# rainbow-gizmo-v2_0.net
KiCad netlist of a schematic drawn in EAGLE
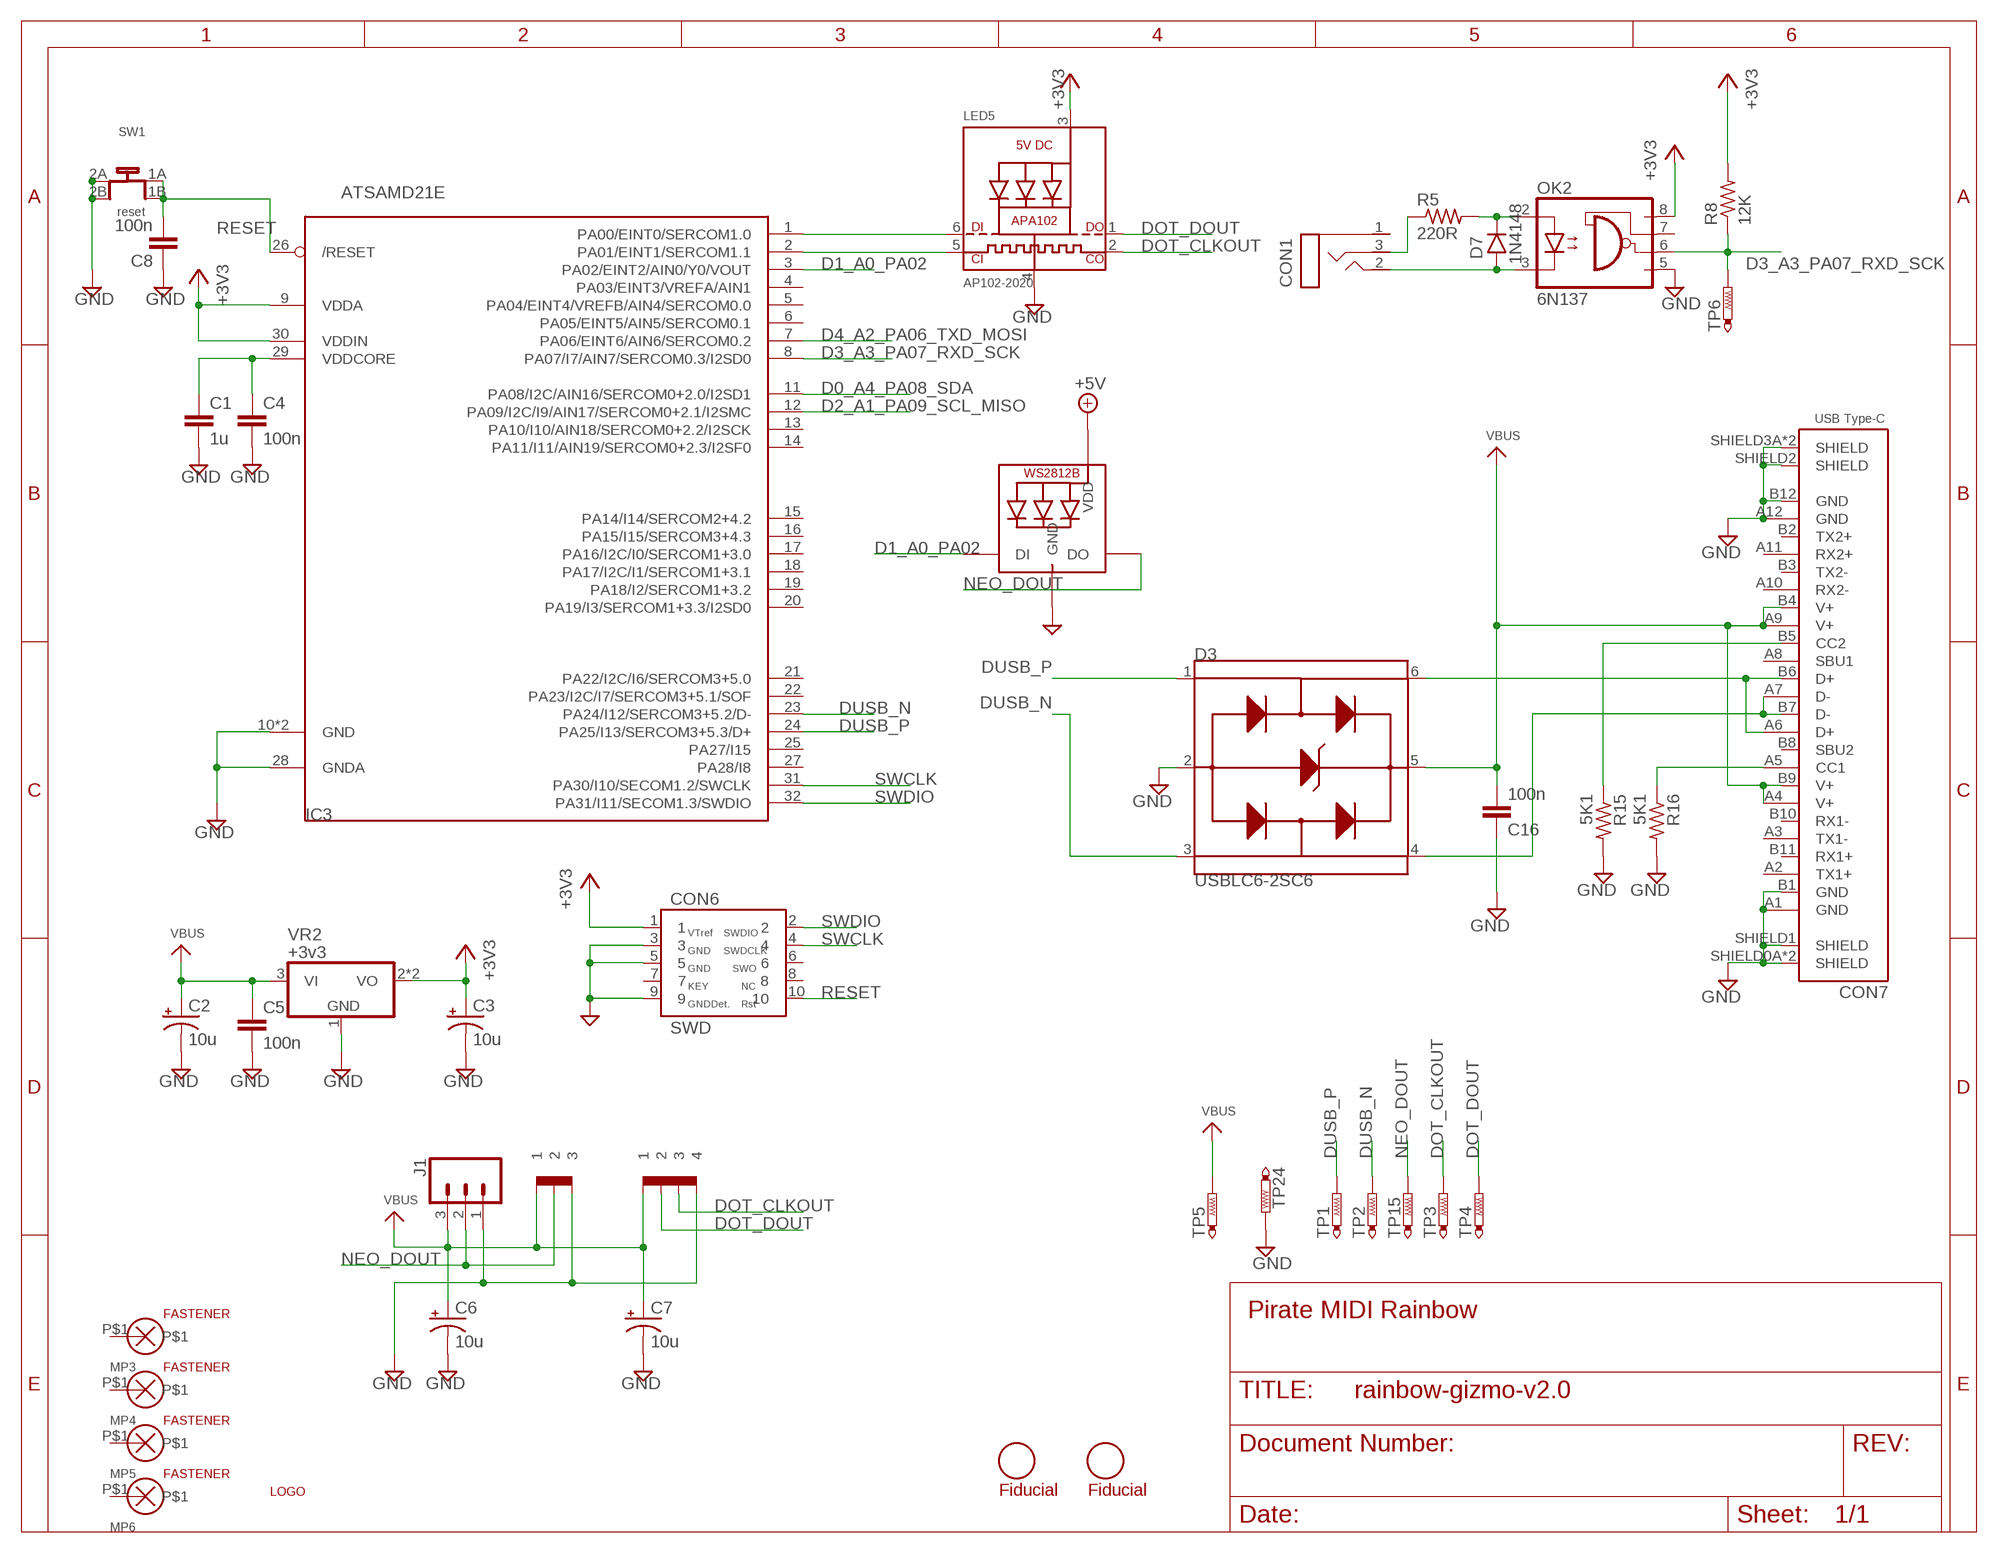
[diagram p0: schematic, sheet 1]

(export (version "E")
  (design (tool "Eeschema 10.0.6"))
  (components
    (comp (ref "C1")
      (value "1u")
      (footprint "eagle-import:0603_CAP")
      (fields
        (field (name "MANUFACTURER") "YAGEO")
        (field (name "PART_NO") "CC0603KRX5R8BB105")
        (field (name "TOLERANCE") "10%")
      )
      (libsource (lib "eagle-import") (part "SMD-NP0603-1U-H"))
    )
    (comp (ref "C2")
      (value "10u")
      (footprint "eagle-import:PANASONIC_B")
      (fields (field (name "MANUFACTURER") "PANASONIC") (field (name "PART_NO") "EEE-HB1E100AR"))
      (libsource (lib "eagle-import") (part "SMD-ELECTROLYTICB_10U"))
    )
    (comp (ref "C3")
      (value "10u")
      (footprint "eagle-import:PANASONIC_B")
      (fields (field (name "MANUFACTURER") "PANASONIC") (field (name "PART_NO") "EEE-HB1E100AR"))
      (libsource (lib "eagle-import") (part "SMD-ELECTROLYTICB_10U"))
    )
    (comp (ref "C4")
      (value "100n")
      (footprint "eagle-import:0603_CAP")
      (fields
        (field (name "MANUFACTURER") "TDK")
        (field (name "PART_NO") "CGA3E2X7R1H104K080AA")
        (field (name "TOLERANCE") "10%")
      )
      (libsource (lib "eagle-import") (part "SMD-NP0603-100N-H"))
    )
    (comp (ref "C5")
      (value "100n")
      (footprint "eagle-import:0603_CAP")
      (fields
        (field (name "MANUFACTURER") "TDK")
        (field (name "PART_NO") "CGA3E2X7R1H104K080AA")
        (field (name "TOLERANCE") "10%")
      )
      (libsource (lib "eagle-import") (part "SMD-NP0603-100N-H"))
    )
    (comp (ref "C6")
      (value "10u")
      (footprint "eagle-import:PANASONIC_B")
      (fields (field (name "MANUFACTURER") "PANASONIC") (field (name "PART_NO") "EEE-HB1E100AR"))
      (libsource (lib "eagle-import") (part "SMD-ELECTROLYTICB_10U"))
    )
    (comp (ref "C7")
      (value "10u")
      (footprint "eagle-import:PANASONIC_B")
      (fields (field (name "MANUFACTURER") "PANASONIC") (field (name "PART_NO") "EEE-HB1E100AR"))
      (libsource (lib "eagle-import") (part "SMD-ELECTROLYTICB_10U"))
    )
    (comp (ref "C8")
      (value "100n")
      (footprint "eagle-import:0603_CAP")
      (fields
        (field (name "MANUFACTURER") "TDK")
        (field (name "PART_NO") "CGA3E2X7R1H104K080AA")
        (field (name "TOLERANCE") "10%")
      )
      (libsource (lib "eagle-import") (part "SMD-NP0603-100N-H"))
    )
    (comp (ref "C16")
      (value "100n")
      (footprint "eagle-import:0603_CAP")
      (fields
        (field (name "MANUFACTURER") "TDK")
        (field (name "PART_NO") "CGA3E2X7R1H104K080AA")
        (field (name "TOLERANCE") "10%")
      )
      (libsource (lib "eagle-import") (part "SMD-NP0603-100N-H"))
    )
    (comp (ref "CON1")
      (value "TRS3.5MM")
      (footprint "eagle-import:SJ-352_-SMT")
      (fields (field (name "MANUFACTURER") "CUI") (field (name "PART_NO") "SJ-3523-SMT-TR"))
      (libsource (lib "eagle-import") (part "TRS3.5MM"))
    )
    (comp (ref "CON2")
      (value "1X3PADS")
      (footprint "eagle-import:1X3_PADS")
      (libsource (lib "eagle-import") (part "1X3PADS"))
    )
    (comp (ref "CON4")
      (value "1X4")
      (footprint "eagle-import:1X4_PADS")
      (libsource (lib "eagle-import") (part "1X4"))
    )
    (comp (ref "CON6")
      (value "SWD")
      (footprint "eagle-import:5X2_1.27MM_SMD")
      (fields (field (name "MANUFACTURER") "HARWIN") (field (name "PART_NO") "M50-3600542R"))
      (libsource (lib "eagle-import") (part "SWD_CONNECTORSMD"))
    )
    (comp (ref "CON7")
      (value "DUAL SMT")
      (footprint "eagle-import:10137064-00021LF")
      (fields (field (name "MANUFACTURER") "AMPHENOL FCI") (field (name "PART_NO") "10137064-00021LF"))
      (libsource (lib "eagle-import") (part "USB_TYPE-CAMPHENOL"))
    )
    (comp (ref "D3")
      (value "USBLC6-2SC6")
      (footprint "eagle-import:SOT95P280X145-6N")
      (fields (field (name "MANUFACTURER") "STMICROELECTRONICS"))
      (libsource (lib "eagle-import") (part "USBLC6-2SC6"))
    )
    (comp (ref "D7")
      (value "1N4148")
      (footprint "eagle-import:SOD-323")
      (fields
        (field (name "MANUFACTURER") "MICRO COMMERCIAL COMPONENTS")
        (field (name "PART_NO") "1N4148WX-TP")
      )
      (libsource (lib "eagle-import") (part "1N4148"))
    )
    (comp (ref "FD3")
      (value "FIDUCIALSQUARE_1MM")
      (footprint "eagle-import:FIDUCIAL_SQUARE_1MM")
      (libsource (lib "eagle-import") (part "FIDUCIALSQUARE_1MM"))
    )
    (comp (ref "FD4")
      (value "FIDUCIALROUND_1MM")
      (footprint "eagle-import:FIDUCIAL_ROUND_1MM")
      (libsource (lib "eagle-import") (part "FIDUCIALROUND_1MM"))
    )
    (comp (ref "IC3")
      (value "ATSAMD21E")
      (footprint "eagle-import:QFN32_5MM")
      (libsource (lib "eagle-import") (part "ATSAMD21E"))
    )
    (comp (ref "J1")
      (value "1X3PH")
      (footprint "eagle-import:JST_S3B-PH-SM4-TB")
      (libsource (lib "eagle-import") (part "1X3PH"))
    )
    (comp (ref "LED1")
      (value "WS2812B2020")
      (footprint "eagle-import:LED2020RGB")
      (fields (field (name "MANUFACTURER") "WORLDSEMI") (field (name "PART_NO") "WS2812B-2020"))
      (libsource (lib "eagle-import") (part "WS2812B2020"))
    )
    (comp (ref "LED5")
      (value "AP102-2020")
      (footprint "eagle-import:APA102_2020")
      (libsource (lib "eagle-import") (part "APA1022020"))
    )
    (comp (ref "MP3")
      (value "SCREW-FASTENER2.5")
      (footprint "eagle-import:M2.5-PANHEAD-VIA")
      (libsource (lib "eagle-import") (part "SCREW-FASTENER2.5"))
    )
    (comp (ref "MP4")
      (value "SCREW-FASTENER2.5")
      (footprint "eagle-import:M2.5-PANHEAD-VIA")
      (libsource (lib "eagle-import") (part "SCREW-FASTENER2.5"))
    )
    (comp (ref "MP5")
      (value "SCREW-FASTENER2.5")
      (footprint "eagle-import:M2.5-PANHEAD-VIA")
      (libsource (lib "eagle-import") (part "SCREW-FASTENER2.5"))
    )
    (comp (ref "MP6")
      (value "SCREW-FASTENER2.5")
      (footprint "eagle-import:M2.5-PANHEAD-VIA")
      (libsource (lib "eagle-import") (part "SCREW-FASTENER2.5"))
    )
    (comp (ref "OK2")
      (value "6N137")
      (footprint "eagle-import:SMD8")
      (fields (field (name "MANUFACTURER") "LITE-ON") (field (name "PART_NO") "6N137S"))
      (libsource (lib "eagle-import") (part "6N137S"))
    )
    (comp (ref "R5")
      (value "220R")
      (footprint "eagle-import:0603-RES")
      (fields (field (name "MANUFACTURER") "YAGEO") (field (name "PART_NO") "RC0603FR-07220RL"))
      (libsource (lib "eagle-import") (part "US0603-220R"))
    )
    (comp (ref "R8")
      (value "12K")
      (footprint "eagle-import:0603-RES")
      (fields (field (name "MANUFACTURER") "YAGEO") (field (name "PART_NO") "RC0603FR-0712KL"))
      (libsource (lib "eagle-import") (part "US0603-12K"))
    )
    (comp (ref "R15")
      (value "5K1")
      (footprint "eagle-import:0603-RES")
      (fields (field (name "MANUFACTURER") "YAGEO") (field (name "PART_NO") "RC0603FR-075K1L"))
      (libsource (lib "eagle-import") (part "US0603-5K1"))
    )
    (comp (ref "R16")
      (value "5K1")
      (footprint "eagle-import:0603-RES")
      (fields (field (name "MANUFACTURER") "YAGEO") (field (name "PART_NO") "RC0603FR-075K1L"))
      (libsource (lib "eagle-import") (part "US0603-5K1"))
    )
    (comp (ref "SW1")
      (value "reset")
      (footprint "eagle-import:KMR_X")
      (fields (field (name "MANUFACTURER") "C&K") (field (name "PART_NO") "KMR621NGLFS"))
      (libsource (lib "eagle-import") (part "MOMENTARYKRM_X"))
    )
    (comp (ref "TP1")
      (value "PTR1B1,27")
      (footprint "eagle-import:B1,27")
      (libsource (lib "eagle-import") (part "PTR1B1,27"))
    )
    (comp (ref "TP2")
      (value "PTR1B1,27")
      (footprint "eagle-import:B1,27")
      (libsource (lib "eagle-import") (part "PTR1B1,27"))
    )
    (comp (ref "TP3")
      (value "PTR1B1,27")
      (footprint "eagle-import:B1,27")
      (libsource (lib "eagle-import") (part "PTR1B1,27"))
    )
    (comp (ref "TP4")
      (value "PTR1B1,27")
      (footprint "eagle-import:B1,27")
      (libsource (lib "eagle-import") (part "PTR1B1,27"))
    )
    (comp (ref "TP5")
      (value "PTR1B1,27")
      (footprint "eagle-import:B1,27")
      (libsource (lib "eagle-import") (part "PTR1B1,27"))
    )
    (comp (ref "TP6")
      (value "PTR1B1,27")
      (footprint "eagle-import:B1,27")
      (libsource (lib "eagle-import") (part "PTR1B1,27"))
    )
    (comp (ref "TP15")
      (value "PTR1B1,27")
      (footprint "eagle-import:B1,27")
      (libsource (lib "eagle-import") (part "PTR1B1,27"))
    )
    (comp (ref "TP24")
      (value "PTR1B1,27")
      (footprint "eagle-import:B1,27")
      (libsource (lib "eagle-import") (part "PTR1B1,27"))
    )
    (comp (ref "U$5")
      (value "PM_LOGOSSTOP_M")
      (footprint "eagle-import:PM_M_MAIN_LOGO1_STOP")
      (libsource (lib "eagle-import") (part "PM_LOGOSSTOP_M"))
    )
    (comp (ref "VR2")
      (value "+3v3")
      (footprint "eagle-import:SOT223")
      (fields (field (name "MANUFACTURER") "STMICROELECTRONICS") (field (name "PART_NO") "LD1117S33CTR"))
      (libsource (lib "eagle-import") (part "LD1117"))
    )
  )
  (nets
    (net (code "1") (name "+3V3") (class "Default")
      (node (ref "C3") (pin "+") (pinfunction "+_+") (pintype "passive"))
      (node (ref "CON6") (pin "1") (pinfunction "1_1") (pintype "passive"))
      (node (ref "IC3") (pin "30") (pinfunction "VDDIN_30") (pintype "power_in"))
      (node (ref "IC3") (pin "9") (pinfunction "VDDA_9") (pintype "power_in"))
      (node (ref "LED5") (pin "3") (pinfunction "VDD_3") (pintype "power_in"))
      (node (ref "OK2") (pin "8") (pinfunction "VCC_8") (pintype "passive"))
      (node (ref "R8") (pin "2") (pinfunction "2_2") (pintype "passive"))
      (node (ref "VR2") (pin "2") (pinfunction "VO_2") (pintype "passive"))
      (node (ref "VR2") (pin "4") (pinfunction "VO_4") (pintype "passive"))
    )
    (net (code "2") (name "+5V") (class "Default")
      (node (ref "LED1") (pin "4") (pinfunction "VDD_4") (pintype "power_in"))
    )
    (net (code "3") (name "/D0_A4_PA08_SDA") (class "Default")
      (node (ref "IC3") (pin "11") (pinfunction "PA08/I2C/AIN16/SERCOM0+2.0/I2SD1_11") (pintype "bidirectional"))
    )
    (net (code "4") (name "/D1_A0_PA02") (class "Default")
      (node (ref "IC3") (pin "3") (pinfunction "PA02/EINT2/AIN0/Y0/VOUT_3") (pintype "bidirectional"))
      (node (ref "LED1") (pin "3") (pinfunction "DI_3") (pintype "input"))
    )
    (net (code "5") (name "/D2_A1_PA09_SCL_MISO") (class "Default")
      (node (ref "IC3") (pin "12") (pinfunction "PA09/I2C/I9/AIN17/SERCOM0+2.1/I2SMC_12") (pintype "bidirectional"))
    )
    (net (code "6") (name "/D3_A3_PA07_RXD_SCK") (class "Default")
      (node (ref "IC3") (pin "8") (pinfunction "PA07/I7/AIN7/SERCOM0.3/I2SD0_8") (pintype "bidirectional"))
      (node (ref "OK2") (pin "6") (pinfunction "VO_6") (pintype "passive"))
      (node (ref "R8") (pin "1") (pinfunction "1_1") (pintype "passive"))
      (node (ref "TP6") (pin "TP") (pinfunction "TP_TP") (pintype "input"))
    )
    (net (code "7") (name "/D4_A2_PA06_TXD_MOSI") (class "Default")
      (node (ref "IC3") (pin "7") (pinfunction "PA06/EINT6/AIN6/SERCOM0.2_7") (pintype "bidirectional"))
    )
    (net (code "8") (name "/DOT_CLKOUT") (class "Default")
      (node (ref "CON4") (pin "P$3") (pinfunction "3_P$3") (pintype "bidirectional"))
      (node (ref "LED5") (pin "2") (pinfunction "CKO_2") (pintype "output"))
      (node (ref "TP3") (pin "TP") (pinfunction "TP_TP") (pintype "input"))
    )
    (net (code "9") (name "/DOT_DOUT") (class "Default")
      (node (ref "CON4") (pin "P$2") (pinfunction "2_P$2") (pintype "bidirectional"))
      (node (ref "LED5") (pin "1") (pinfunction "DO_1") (pintype "output"))
      (node (ref "TP4") (pin "TP") (pinfunction "TP_TP") (pintype "input"))
    )
    (net (code "10") (name "/DUSB_N") (class "Default")
      (node (ref "D3") (pin "3") (pinfunction "I/O2_3") (pintype "bidirectional"))
      (node (ref "IC3") (pin "23") (pinfunction "PA24/I12/SERCOM3+5.2/D-_23") (pintype "bidirectional"))
      (node (ref "TP2") (pin "TP") (pinfunction "TP_TP") (pintype "input"))
    )
    (net (code "11") (name "/DUSB_P") (class "Default")
      (node (ref "D3") (pin "1") (pinfunction "I/O1_1") (pintype "bidirectional"))
      (node (ref "IC3") (pin "24") (pinfunction "PA25/I13/SERCOM3+5.3/D+_24") (pintype "bidirectional"))
      (node (ref "TP1") (pin "TP") (pinfunction "TP_TP") (pintype "input"))
    )
    (net (code "12") (name "/NEO_DOUT") (class "Default")
      (node (ref "CON2") (pin "P$2") (pinfunction "2_P$2") (pintype "bidirectional"))
      (node (ref "J1") (pin "2") (pinfunction "2_2") (pintype "passive"))
      (node (ref "LED1") (pin "1") (pinfunction "DO_1") (pintype "output"))
      (node (ref "TP15") (pin "TP") (pinfunction "TP_TP") (pintype "input"))
    )
    (net (code "13") (name "/RESET") (class "Default")
      (node (ref "C8") (pin "2") (pinfunction "2_2") (pintype "passive"))
      (node (ref "CON6") (pin "10") (pinfunction "10_10") (pintype "passive"))
      (node (ref "IC3") (pin "26") (pinfunction "/RESET_26") (pintype "bidirectional"))
      (node (ref "SW1") (pin "1A") (pinfunction "1_1A") (pintype "passive"))
      (node (ref "SW1") (pin "1B") (pinfunction "2_1B") (pintype "passive"))
    )
    (net (code "14") (name "/SWCLK") (class "Default")
      (node (ref "CON6") (pin "4") (pinfunction "4_4") (pintype "passive"))
      (node (ref "IC3") (pin "31") (pinfunction "PA30/I10/SECOM1.2/SWCLK_31") (pintype "bidirectional"))
    )
    (net (code "15") (name "/SWDIO") (class "Default")
      (node (ref "CON6") (pin "2") (pinfunction "2_2") (pintype "passive"))
      (node (ref "IC3") (pin "32") (pinfunction "PA31/I11/SECOM1.3/SWDIO_32") (pintype "bidirectional"))
    )
    (net (code "16") (name "GND") (class "Default")
      (node (ref "C1") (pin "2") (pinfunction "2_2") (pintype "passive"))
      (node (ref "C16") (pin "1") (pinfunction "1_1") (pintype "passive"))
      (node (ref "C2") (pin "-") (pinfunction "-_-") (pintype "passive"))
      (node (ref "C3") (pin "-") (pinfunction "-_-") (pintype "passive"))
      (node (ref "C4") (pin "2") (pinfunction "2_2") (pintype "passive"))
      (node (ref "C5") (pin "2") (pinfunction "2_2") (pintype "passive"))
      (node (ref "C6") (pin "-") (pinfunction "-_-") (pintype "passive"))
      (node (ref "C7") (pin "-") (pinfunction "-_-") (pintype "passive"))
      (node (ref "C8") (pin "1") (pinfunction "1_1") (pintype "passive"))
      (node (ref "CON2") (pin "P$3") (pinfunction "3_P$3") (pintype "bidirectional"))
      (node (ref "CON4") (pin "P$4") (pinfunction "4_P$4") (pintype "bidirectional"))
      (node (ref "CON6") (pin "3") (pinfunction "3_3") (pintype "passive"))
      (node (ref "CON6") (pin "5") (pinfunction "5_5") (pintype "passive"))
      (node (ref "CON6") (pin "9") (pinfunction "9_9") (pintype "passive"))
      (node (ref "CON7") (pin "A1") (pinfunction "GND_A1") (pintype "power_in"))
      (node (ref "CON7") (pin "A12") (pinfunction "GND_A12") (pintype "power_in"))
      (node (ref "CON7") (pin "B1") (pinfunction "GND_B1") (pintype "power_in"))
      (node (ref "CON7") (pin "B12") (pinfunction "GND_B12") (pintype "power_in"))
      (node (ref "CON7") (pin "SHIELD0A") (pinfunction "SHIELD_SHIELD0A") (pintype "bidirectional"))
      (node (ref "CON7") (pin "SHIELD0B") (pinfunction "SHIELD_SHIELD0B") (pintype "bidirectional"))
      (node (ref "CON7") (pin "SHIELD1") (pinfunction "SHIELD_SHIELD1") (pintype "bidirectional"))
      (node (ref "CON7") (pin "SHIELD2") (pinfunction "SHIELD_SHIELD2") (pintype "bidirectional"))
      (node (ref "CON7") (pin "SHIELD3A") (pinfunction "SHIELD_SHIELD3A") (pintype "bidirectional"))
      (node (ref "CON7") (pin "SHIELD3B") (pinfunction "SHIELD_SHIELD3B") (pintype "bidirectional"))
      (node (ref "D3") (pin "2") (pinfunction "GND_2") (pintype "power_in"))
      (node (ref "IC3") (pin "10") (pinfunction "GND_10") (pintype "power_in"))
      (node (ref "IC3") (pin "28") (pinfunction "GNDA_28") (pintype "power_in"))
      (node (ref "IC3") (pin "33") (pinfunction "GND_33") (pintype "power_in"))
      (node (ref "J1") (pin "1") (pinfunction "1_1") (pintype "passive"))
      (node (ref "LED1") (pin "2") (pinfunction "GND_2") (pintype "power_in"))
      (node (ref "LED5") (pin "4") (pinfunction "GND_4") (pintype "power_in"))
      (node (ref "OK2") (pin "5") (pinfunction "GND_5") (pintype "passive"))
      (node (ref "R15") (pin "2") (pinfunction "2_2") (pintype "passive"))
      (node (ref "R16") (pin "2") (pinfunction "2_2") (pintype "passive"))
      (node (ref "SW1") (pin "2A") (pinfunction "3_2A") (pintype "passive"))
      (node (ref "SW1") (pin "2B") (pinfunction "4_2B") (pintype "passive"))
      (node (ref "TP24") (pin "TP") (pinfunction "TP_TP") (pintype "input"))
      (node (ref "VR2") (pin "1") (pinfunction "GND_1") (pintype "passive"))
    )
    (net (code "17") (name "Net-(CON1-R)") (class "Default")
      (node (ref "CON1") (pin "3") (pinfunction "R_3") (pintype "passive"))
      (node (ref "R5") (pin "1") (pinfunction "1_1") (pintype "passive"))
    )
    (net (code "18") (name "Net-(CON1-T)") (class "Default")
      (node (ref "CON1") (pin "2") (pinfunction "T_2") (pintype "passive"))
      (node (ref "D7") (pin "A") (pinfunction "A_A") (pintype "passive"))
      (node (ref "OK2") (pin "3") (pinfunction "C_3") (pintype "passive"))
    )
    (net (code "19") (name "Net-(CON7-CC1)") (class "Default")
      (node (ref "CON7") (pin "A5") (pinfunction "CC1_A5") (pintype "bidirectional"))
      (node (ref "R16") (pin "1") (pinfunction "1_1") (pintype "passive"))
    )
    (net (code "20") (name "Net-(CON7-CC2)") (class "Default")
      (node (ref "CON7") (pin "B5") (pinfunction "CC2_B5") (pintype "bidirectional"))
      (node (ref "R15") (pin "1") (pinfunction "1_1") (pintype "passive"))
    )
    (net (code "21") (name "Net-(D3-I{slash}O3)") (class "Default")
      (node (ref "CON7") (pin "A6") (pinfunction "D+_A6") (pintype "bidirectional"))
      (node (ref "CON7") (pin "B6") (pinfunction "D+_B6") (pintype "bidirectional"))
      (node (ref "D3") (pin "6") (pinfunction "I/O3_6") (pintype "bidirectional"))
    )
    (net (code "22") (name "Net-(D3-I{slash}O4)") (class "Default")
      (node (ref "CON7") (pin "A7") (pinfunction "D-_A7") (pintype "bidirectional"))
      (node (ref "CON7") (pin "B7") (pinfunction "D-_B7") (pintype "bidirectional"))
      (node (ref "D3") (pin "4") (pinfunction "I/O4_4") (pintype "bidirectional"))
    )
    (net (code "23") (name "Net-(IC3-PA00{slash}EINT0{slash}SERCOM1.0)") (class "Default")
      (node (ref "IC3") (pin "1") (pinfunction "PA00/EINT0/SERCOM1.0_1") (pintype "bidirectional"))
      (node (ref "LED5") (pin "6") (pinfunction "DI_6") (pintype "input"))
    )
    (net (code "24") (name "Net-(IC3-PA01{slash}EINT1{slash}SERCOM1.1)") (class "Default")
      (node (ref "IC3") (pin "2") (pinfunction "PA01/EINT1/SERCOM1.1_2") (pintype "bidirectional"))
      (node (ref "LED5") (pin "5") (pinfunction "CKI_5") (pintype "input"))
    )
    (net (code "25") (name "Net-(IC3-VDDCORE)") (class "Default")
      (node (ref "C1") (pin "1") (pinfunction "1_1") (pintype "passive"))
      (node (ref "C4") (pin "1") (pinfunction "1_1") (pintype "passive"))
      (node (ref "IC3") (pin "29") (pinfunction "VDDCORE_29") (pintype "power_in"))
    )
    (net (code "26") (name "Net-(OK2-A)") (class "Default")
      (node (ref "D7") (pin "C") (pinfunction "C_C") (pintype "passive"))
      (node (ref "OK2") (pin "2") (pinfunction "A_2") (pintype "passive"))
      (node (ref "R5") (pin "2") (pinfunction "2_2") (pintype "passive"))
    )
    (net (code "27") (name "VBUS") (class "Default")
      (node (ref "C16") (pin "2") (pinfunction "2_2") (pintype "passive"))
      (node (ref "C2") (pin "+") (pinfunction "+_+") (pintype "passive"))
      (node (ref "C5") (pin "1") (pinfunction "1_1") (pintype "passive"))
      (node (ref "C6") (pin "+") (pinfunction "+_+") (pintype "passive"))
      (node (ref "C7") (pin "+") (pinfunction "+_+") (pintype "passive"))
      (node (ref "CON2") (pin "P$1") (pinfunction "1_P$1") (pintype "bidirectional"))
      (node (ref "CON4") (pin "P$1") (pinfunction "1_P$1") (pintype "bidirectional"))
      (node (ref "CON7") (pin "A4") (pinfunction "V+_A4") (pintype "power_in"))
      (node (ref "CON7") (pin "A9") (pinfunction "V+_A9") (pintype "power_in"))
      (node (ref "CON7") (pin "B4") (pinfunction "V+_B4") (pintype "power_in"))
      (node (ref "CON7") (pin "B9") (pinfunction "V+_B9") (pintype "power_in"))
      (node (ref "D3") (pin "5") (pinfunction "VBUS_5") (pintype "power_in"))
      (node (ref "J1") (pin "3") (pinfunction "3_3") (pintype "passive"))
      (node (ref "TP5") (pin "TP") (pinfunction "TP_TP") (pintype "input"))
      (node (ref "VR2") (pin "3") (pinfunction "VI_3") (pintype "input"))
    )
    (net (code "28") (name "unconnected-(CON1-S-Pad1)") (class "Default")
      (node (ref "CON1") (pin "1") (pinfunction "S_1") (pintype "passive"))
    )
    (net (code "29") (name "unconnected-(CON6-Pad6)") (class "Default")
      (node (ref "CON6") (pin "6") (pinfunction "6_6") (pintype "passive"))
    )
    (net (code "30") (name "unconnected-(CON6-Pad7)") (class "Default")
      (node (ref "CON6") (pin "7") (pinfunction "7_7") (pintype "passive"))
    )
    (net (code "31") (name "unconnected-(CON6-Pad8)") (class "Default")
      (node (ref "CON6") (pin "8") (pinfunction "8_8") (pintype "passive"))
    )
    (net (code "32") (name "unconnected-(CON7-RX1+-PadB11)") (class "Default")
      (node (ref "CON7") (pin "B11") (pinfunction "RX1+_B11") (pintype "input"))
    )
    (net (code "33") (name "unconnected-(CON7-RX1--PadB10)") (class "Default")
      (node (ref "CON7") (pin "B10") (pinfunction "RX1-_B10") (pintype "input"))
    )
    (net (code "34") (name "unconnected-(CON7-RX2+-PadA11)") (class "Default")
      (node (ref "CON7") (pin "A11") (pinfunction "RX2+_A11") (pintype "input"))
    )
    (net (code "35") (name "unconnected-(CON7-RX2--PadA10)") (class "Default")
      (node (ref "CON7") (pin "A10") (pinfunction "RX2-_A10") (pintype "input"))
    )
    (net (code "36") (name "unconnected-(CON7-SBU1-PadA8)") (class "Default")
      (node (ref "CON7") (pin "A8") (pinfunction "SBU1_A8") (pintype "bidirectional"))
    )
    (net (code "37") (name "unconnected-(CON7-SBU2-PadB8)") (class "Default")
      (node (ref "CON7") (pin "B8") (pinfunction "SBU2_B8") (pintype "bidirectional"))
    )
    (net (code "38") (name "unconnected-(CON7-TX1+-PadA2)") (class "Default")
      (node (ref "CON7") (pin "A2") (pinfunction "TX1+_A2") (pintype "output"))
    )
    (net (code "39") (name "unconnected-(CON7-TX1--PadA3)") (class "Default")
      (node (ref "CON7") (pin "A3") (pinfunction "TX1-_A3") (pintype "output"))
    )
    (net (code "40") (name "unconnected-(CON7-TX2+-PadB2)") (class "Default")
      (node (ref "CON7") (pin "B2") (pinfunction "TX2+_B2") (pintype "output"))
    )
    (net (code "41") (name "unconnected-(CON7-TX2--PadB3)") (class "Default")
      (node (ref "CON7") (pin "B3") (pinfunction "TX2-_B3") (pintype "output"))
    )
    (net (code "42") (name "unconnected-(IC3-PA03{slash}EINT3{slash}VREFA{slash}AIN1-Pad4)") (class "Default")
      (node (ref "IC3") (pin "4") (pinfunction "PA03/EINT3/VREFA/AIN1_4") (pintype "bidirectional"))
    )
    (net (code "43") (name "unconnected-(IC3-PA04{slash}EINT4{slash}VREFB{slash}AIN4{slash}SERCOM0.0-Pad5)") (class "Default")
      (node (ref "IC3") (pin "5") (pinfunction "PA04/EINT4/VREFB/AIN4/SERCOM0.0_5") (pintype "bidirectional"))
    )
    (net (code "44") (name "unconnected-(IC3-PA05{slash}EINT5{slash}AIN5{slash}SERCOM0.1-Pad6)") (class "Default")
      (node (ref "IC3") (pin "6") (pinfunction "PA05/EINT5/AIN5/SERCOM0.1_6") (pintype "bidirectional"))
    )
    (net (code "45") (name "unconnected-(IC3-PA10{slash}I10{slash}AIN18{slash}SERCOM0+2.2{slash}I2SCK-Pad13)") (class "Default")
      (node (ref "IC3") (pin "13") (pinfunction "PA10/I10/AIN18/SERCOM0+2.2/I2SCK_13") (pintype "bidirectional"))
    )
    (net (code "46") (name "unconnected-(IC3-PA11{slash}I11{slash}AIN19{slash}SERCOM0+2.3{slash}I2SF0-Pad14)") (class "Default")
      (node (ref "IC3") (pin "14") (pinfunction "PA11/I11/AIN19/SERCOM0+2.3/I2SF0_14") (pintype "bidirectional"))
    )
    (net (code "47") (name "unconnected-(IC3-PA14{slash}I14{slash}SERCOM2+4.2-Pad15)") (class "Default")
      (node (ref "IC3") (pin "15") (pinfunction "PA14/I14/SERCOM2+4.2_15") (pintype "bidirectional"))
    )
    (net (code "48") (name "unconnected-(IC3-PA15{slash}I15{slash}SERCOM3+4.3-Pad16)") (class "Default")
      (node (ref "IC3") (pin "16") (pinfunction "PA15/I15/SERCOM3+4.3_16") (pintype "bidirectional"))
    )
    (net (code "49") (name "unconnected-(IC3-PA16{slash}I2C{slash}I0{slash}SERCOM1+3.0-Pad17)") (class "Default")
      (node (ref "IC3") (pin "17") (pinfunction "PA16/I2C/I0/SERCOM1+3.0_17") (pintype "bidirectional"))
    )
    (net (code "50") (name "unconnected-(IC3-PA17{slash}I2C{slash}I1{slash}SERCOM1+3.1-Pad18)") (class "Default")
      (node (ref "IC3") (pin "18") (pinfunction "PA17/I2C/I1/SERCOM1+3.1_18") (pintype "bidirectional"))
    )
    (net (code "51") (name "unconnected-(IC3-PA18{slash}I2{slash}SERCOM1+3.2-Pad19)") (class "Default")
      (node (ref "IC3") (pin "19") (pinfunction "PA18/I2/SERCOM1+3.2_19") (pintype "bidirectional"))
    )
    (net (code "52") (name "unconnected-(IC3-PA19{slash}I3{slash}SERCOM1+3.3{slash}I2SD0-Pad20)") (class "Default")
      (node (ref "IC3") (pin "20") (pinfunction "PA19/I3/SERCOM1+3.3/I2SD0_20") (pintype "bidirectional"))
    )
    (net (code "53") (name "unconnected-(IC3-PA22{slash}I2C{slash}I6{slash}SERCOM3+5.0-Pad21)") (class "Default")
      (node (ref "IC3") (pin "21") (pinfunction "PA22/I2C/I6/SERCOM3+5.0_21") (pintype "bidirectional"))
    )
    (net (code "54") (name "unconnected-(IC3-PA23{slash}I2C{slash}I7{slash}SERCOM3+5.1{slash}SOF-Pad22)") (class "Default")
      (node (ref "IC3") (pin "22") (pinfunction "PA23/I2C/I7/SERCOM3+5.1/SOF_22") (pintype "bidirectional"))
    )
    (net (code "55") (name "unconnected-(IC3-PA27{slash}I15-Pad25)") (class "Default")
      (node (ref "IC3") (pin "25") (pinfunction "PA27/I15_25") (pintype "bidirectional"))
    )
    (net (code "56") (name "unconnected-(IC3-PA28{slash}I8-Pad27)") (class "Default")
      (node (ref "IC3") (pin "27") (pinfunction "PA28/I8_27") (pintype "bidirectional"))
    )
    (net (code "57") (name "unconnected-(MP3-PadP$1)") (class "Default")
      (node (ref "MP3") (pin "P$1") (pinfunction "P$1_P$1") (pintype "bidirectional"))
    )
    (net (code "58") (name "unconnected-(MP4-PadP$1)") (class "Default")
      (node (ref "MP4") (pin "P$1") (pinfunction "P$1_P$1") (pintype "bidirectional"))
    )
    (net (code "59") (name "unconnected-(MP5-PadP$1)") (class "Default")
      (node (ref "MP5") (pin "P$1") (pinfunction "P$1_P$1") (pintype "bidirectional"))
    )
    (net (code "60") (name "unconnected-(MP6-PadP$1)") (class "Default")
      (node (ref "MP6") (pin "P$1") (pinfunction "P$1_P$1") (pintype "bidirectional"))
    )
    (net (code "61") (name "unconnected-(OK2-VE-Pad7)") (class "Default")
      (node (ref "OK2") (pin "7") (pinfunction "VE_7") (pintype "passive"))
    )
  )
)
